# Power_LED_Inducators.net
KiCad netlist of a schematic drawn in Altium Designer
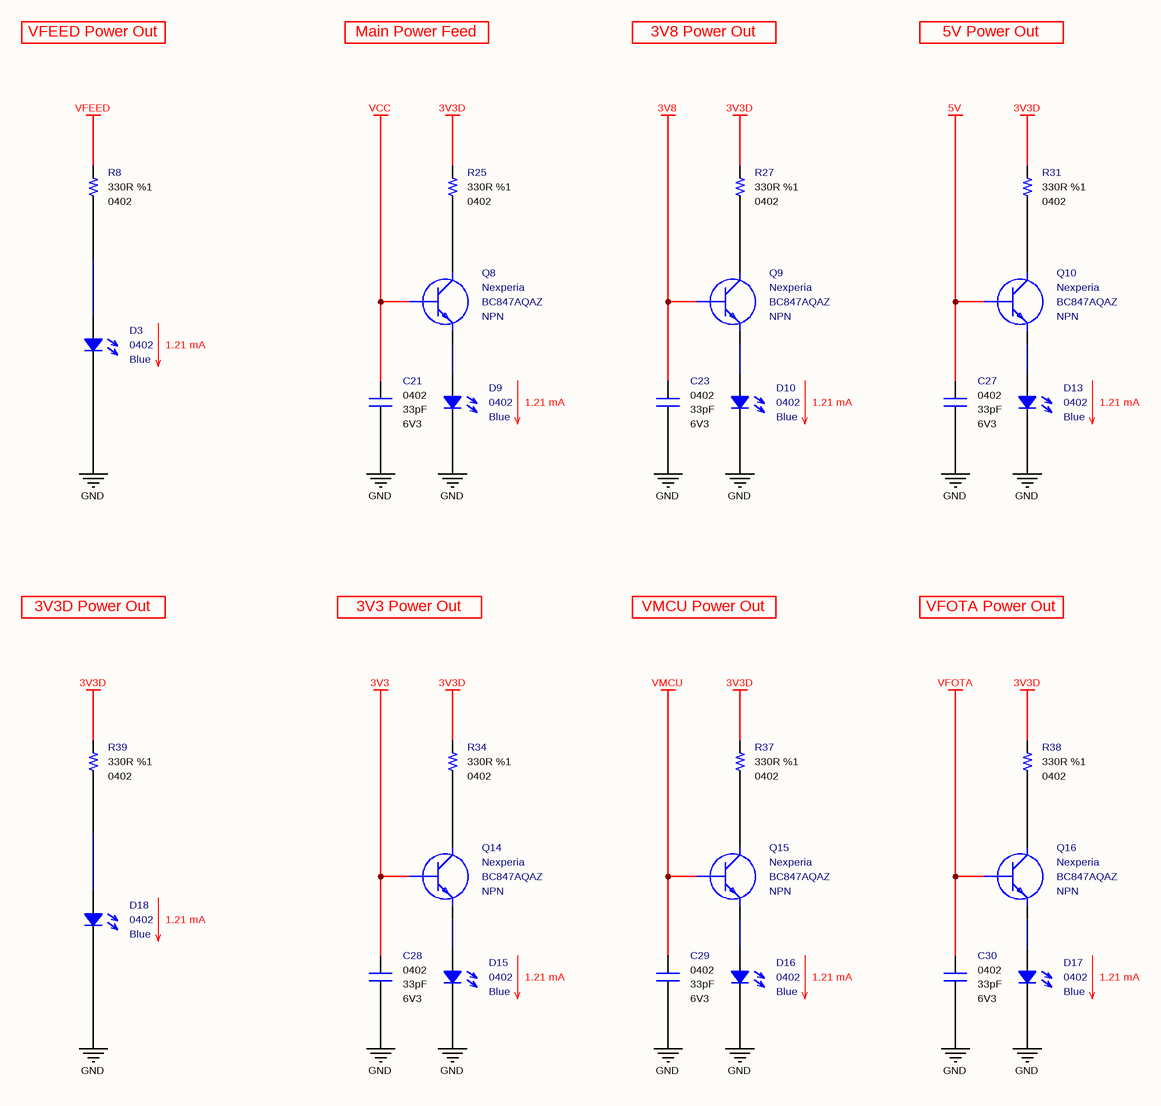
[diagram p0: Power LED Inducators.SchDoc]

(export (version "E")
  (design (tool "Eeschema 10.0.6"))
  (components
    (comp (ref "C21")
      (value "33pF")
      (footprint "CAPACITOR_0402")
      (description "Capacitor - 33pF [0402] (Ceramic)")
      (fields
        (field (name "CASE") "0402")
        (field (name "TOLERANCE") "10%")
        (field (name "VOLTAGE") "6V3")
        (field (name "MANUFACTURER PART NUMBER") "C0402C330J9RACAUTO")
      )
      (libsource (lib "Ovoo_Library") (part "Capacitor - 33pF [0402-6V3]"))
    )
    (comp (ref "C23")
      (value "33pF")
      (footprint "CAPACITOR_0402")
      (description "Capacitor - 33pF [0402] (Ceramic)")
      (fields
        (field (name "CASE") "0402")
        (field (name "TOLERANCE") "10%")
        (field (name "VOLTAGE") "6V3")
        (field (name "MANUFACTURER PART NUMBER") "C0402C330J9RACAUTO")
      )
      (libsource (lib "Ovoo_Library") (part "Capacitor - 33pF [0402-6V3]"))
    )
    (comp (ref "C27")
      (value "33pF")
      (footprint "CAPACITOR_0402")
      (description "Capacitor - 33pF [0402] (Ceramic)")
      (fields
        (field (name "CASE") "0402")
        (field (name "TOLERANCE") "10%")
        (field (name "VOLTAGE") "6V3")
        (field (name "MANUFACTURER PART NUMBER") "C0402C330J9RACAUTO")
      )
      (libsource (lib "Ovoo_Library") (part "Capacitor - 33pF [0402-6V3]"))
    )
    (comp (ref "C28")
      (value "33pF")
      (footprint "CAPACITOR_0402")
      (description "Capacitor - 33pF [0402] (Ceramic)")
      (fields
        (field (name "CASE") "0402")
        (field (name "TOLERANCE") "10%")
        (field (name "VOLTAGE") "6V3")
        (field (name "MANUFACTURER PART NUMBER") "C0402C330J9RACAUTO")
      )
      (libsource (lib "Ovoo_Library") (part "Capacitor - 33pF [0402-6V3]"))
    )
    (comp (ref "C29")
      (value "33pF")
      (footprint "CAPACITOR_0402")
      (description "Capacitor - 33pF [0402] (Ceramic)")
      (fields
        (field (name "CASE") "0402")
        (field (name "TOLERANCE") "10%")
        (field (name "VOLTAGE") "6V3")
        (field (name "MANUFACTURER PART NUMBER") "C0402C330J9RACAUTO")
      )
      (libsource (lib "Ovoo_Library") (part "Capacitor - 33pF [0402-6V3]"))
    )
    (comp (ref "C30")
      (value "33pF")
      (footprint "CAPACITOR_0402")
      (description "Capacitor - 33pF [0402] (Ceramic)")
      (fields
        (field (name "CASE") "0402")
        (field (name "TOLERANCE") "10%")
        (field (name "VOLTAGE") "6V3")
        (field (name "MANUFACTURER PART NUMBER") "C0402C330J9RACAUTO")
      )
      (libsource (lib "Ovoo_Library") (part "Capacitor - 33pF [0402-6V3]"))
    )
    (comp (ref "D3")
      (value "SMD LED (Blue)")
      (footprint "LED_0402")
      (description "Standard LEDs - SMD PICOLEDTM;BLUE LED; 25M @ 5MA")
      (fields
        (field (name "MANUFACTURER_PART_NUMBER") "SMLP13BC8TT86")
        (field (name "MOUSER_PART_NUMBER") "755-SMLP13BC8TT86")
        (field (name "CASE") "0402")
        (field (name "COLOR") "Blue")
      )
      (libsource (lib "Ovoo_Library") (part "Diode - LED (0402-Blue)"))
    )
    (comp (ref "D9")
      (value "SMD LED (Blue)")
      (footprint "LED_0402")
      (description "Standard LEDs - SMD PICOLEDTM;BLUE LED; 25M @ 5MA")
      (fields
        (field (name "MANUFACTURER_PART_NUMBER") "SMLP13BC8TT86")
        (field (name "MOUSER_PART_NUMBER") "755-SMLP13BC8TT86")
        (field (name "CASE") "0402")
        (field (name "COLOR") "Blue")
      )
      (libsource (lib "Ovoo_Library") (part "Diode - LED (0402-Blue)"))
    )
    (comp (ref "D10")
      (value "SMD LED (Blue)")
      (footprint "LED_0402")
      (description "Standard LEDs - SMD PICOLEDTM;BLUE LED; 25M @ 5MA")
      (fields
        (field (name "MANUFACTURER_PART_NUMBER") "SMLP13BC8TT86")
        (field (name "MOUSER_PART_NUMBER") "755-SMLP13BC8TT86")
        (field (name "CASE") "0402")
        (field (name "COLOR") "Blue")
      )
      (libsource (lib "Ovoo_Library") (part "Diode - LED (0402-Blue)"))
    )
    (comp (ref "D13")
      (value "SMD LED (Blue)")
      (footprint "LED_0402")
      (description "Standard LEDs - SMD PICOLEDTM;BLUE LED; 25M @ 5MA")
      (fields
        (field (name "MANUFACTURER_PART_NUMBER") "SMLP13BC8TT86")
        (field (name "MOUSER_PART_NUMBER") "755-SMLP13BC8TT86")
        (field (name "CASE") "0402")
        (field (name "COLOR") "Blue")
      )
      (libsource (lib "Ovoo_Library") (part "Diode - LED (0402-Blue)"))
    )
    (comp (ref "D15")
      (value "SMD LED (Blue)")
      (footprint "LED_0402")
      (description "Standard LEDs - SMD PICOLEDTM;BLUE LED; 25M @ 5MA")
      (fields
        (field (name "MANUFACTURER_PART_NUMBER") "SMLP13BC8TT86")
        (field (name "MOUSER_PART_NUMBER") "755-SMLP13BC8TT86")
        (field (name "CASE") "0402")
        (field (name "COLOR") "Blue")
      )
      (libsource (lib "Ovoo_Library") (part "Diode - LED (0402-Blue)"))
    )
    (comp (ref "D16")
      (value "SMD LED (Blue)")
      (footprint "LED_0402")
      (description "Standard LEDs - SMD PICOLEDTM;BLUE LED; 25M @ 5MA")
      (fields
        (field (name "MANUFACTURER_PART_NUMBER") "SMLP13BC8TT86")
        (field (name "MOUSER_PART_NUMBER") "755-SMLP13BC8TT86")
        (field (name "CASE") "0402")
        (field (name "COLOR") "Blue")
      )
      (libsource (lib "Ovoo_Library") (part "Diode - LED (0402-Blue)"))
    )
    (comp (ref "D17")
      (value "SMD LED (Blue)")
      (footprint "LED_0402")
      (description "Standard LEDs - SMD PICOLEDTM;BLUE LED; 25M @ 5MA")
      (fields
        (field (name "MANUFACTURER_PART_NUMBER") "SMLP13BC8TT86")
        (field (name "MOUSER_PART_NUMBER") "755-SMLP13BC8TT86")
        (field (name "CASE") "0402")
        (field (name "COLOR") "Blue")
      )
      (libsource (lib "Ovoo_Library") (part "Diode - LED (0402-Blue)"))
    )
    (comp (ref "D18")
      (value "SMD LED (Blue)")
      (footprint "LED_0402")
      (description "Standard LEDs - SMD PICOLEDTM;BLUE LED; 25M @ 5MA")
      (fields
        (field (name "MANUFACTURER_PART_NUMBER") "SMLP13BC8TT86")
        (field (name "MOUSER_PART_NUMBER") "755-SMLP13BC8TT86")
        (field (name "CASE") "0402")
        (field (name "COLOR") "Blue")
      )
      (libsource (lib "Ovoo_Library") (part "Diode - LED (0402-Blue)"))
    )
    (comp (ref "Q8")
      (value "Bipolar NPN Transistors")
      (footprint "SOT1215")
      (description "Bipolar Transistors - BJT BC847AQA/DFN1010D-3/REEL 7\" Q2")
      (fields
        (field (name "MOUSER_PART_NUMBER") "771-BC847AQAZ")
        (field (name "MANUFACTURER_NAME") "Nexperia")
        (field (name "MANUFACTURER_PART_NUMBER") "BC847AQAZ")
        (field (name "POLARITY") "NPN")
      )
      (libsource (lib "Ovoo_Library") (part "Transistor - BC847"))
    )
    (comp (ref "Q9")
      (value "Bipolar NPN Transistors")
      (footprint "SOT1215")
      (description "Bipolar Transistors - BJT BC847AQA/DFN1010D-3/REEL 7\" Q2")
      (fields
        (field (name "MOUSER_PART_NUMBER") "771-BC847AQAZ")
        (field (name "MANUFACTURER_NAME") "Nexperia")
        (field (name "MANUFACTURER_PART_NUMBER") "BC847AQAZ")
        (field (name "POLARITY") "NPN")
      )
      (libsource (lib "Ovoo_Library") (part "Transistor - BC847"))
    )
    (comp (ref "Q10")
      (value "Bipolar NPN Transistors")
      (footprint "SOT1215")
      (description "Bipolar Transistors - BJT BC847AQA/DFN1010D-3/REEL 7\" Q2")
      (fields
        (field (name "MOUSER_PART_NUMBER") "771-BC847AQAZ")
        (field (name "MANUFACTURER_NAME") "Nexperia")
        (field (name "MANUFACTURER_PART_NUMBER") "BC847AQAZ")
        (field (name "POLARITY") "NPN")
      )
      (libsource (lib "Ovoo_Library") (part "Transistor - BC847"))
    )
    (comp (ref "Q14")
      (value "Bipolar NPN Transistors")
      (footprint "SOT1215")
      (description "Bipolar Transistors - BJT BC847AQA/DFN1010D-3/REEL 7\" Q2")
      (fields
        (field (name "MOUSER_PART_NUMBER") "771-BC847AQAZ")
        (field (name "MANUFACTURER_NAME") "Nexperia")
        (field (name "MANUFACTURER_PART_NUMBER") "BC847AQAZ")
        (field (name "POLARITY") "NPN")
      )
      (libsource (lib "Ovoo_Library") (part "Transistor - BC847"))
    )
    (comp (ref "Q15")
      (value "Bipolar NPN Transistors")
      (footprint "SOT1215")
      (description "Bipolar Transistors - BJT BC847AQA/DFN1010D-3/REEL 7\" Q2")
      (fields
        (field (name "MOUSER_PART_NUMBER") "771-BC847AQAZ")
        (field (name "MANUFACTURER_NAME") "Nexperia")
        (field (name "MANUFACTURER_PART_NUMBER") "BC847AQAZ")
        (field (name "POLARITY") "NPN")
      )
      (libsource (lib "Ovoo_Library") (part "Transistor - BC847"))
    )
    (comp (ref "Q16")
      (value "Bipolar NPN Transistors")
      (footprint "SOT1215")
      (description "Bipolar Transistors - BJT BC847AQA/DFN1010D-3/REEL 7\" Q2")
      (fields
        (field (name "MOUSER_PART_NUMBER") "771-BC847AQAZ")
        (field (name "MANUFACTURER_NAME") "Nexperia")
        (field (name "MANUFACTURER_PART_NUMBER") "BC847AQAZ")
        (field (name "POLARITY") "NPN")
      )
      (libsource (lib "Ovoo_Library") (part "Transistor - BC847"))
    )
    (comp (ref "R8")
      (value "330R")
      (footprint "RESISTOR_0402")
      (description "Thick Film Resistors - SMD 1/16 W 330 Ohm 1%")
      (fields
        (field (name "TOLERANCE") "%1")
        (field (name "CASE") "0402")
        (field (name "MANUFACTURER PART NUMBER") "CRCW0402330RFKED")
        (field (name "MOUSER PART NUMBER") "71-CRCW0402-330-E3")
      )
      (libsource (lib "Ovoo_Library") (part "Resistor - 330R"))
    )
    (comp (ref "R25")
      (value "330R")
      (footprint "RESISTOR_0402")
      (description "Thick Film Resistors - SMD 1/16 W 330 Ohm 1%")
      (fields
        (field (name "TOLERANCE") "%1")
        (field (name "CASE") "0402")
        (field (name "MANUFACTURER PART NUMBER") "CRCW0402330RFKED")
        (field (name "MOUSER PART NUMBER") "71-CRCW0402-330-E3")
      )
      (libsource (lib "Ovoo_Library") (part "Resistor - 330R"))
    )
    (comp (ref "R27")
      (value "330R")
      (footprint "RESISTOR_0402")
      (description "Thick Film Resistors - SMD 1/16 W 330 Ohm 1%")
      (fields
        (field (name "TOLERANCE") "%1")
        (field (name "CASE") "0402")
        (field (name "MANUFACTURER PART NUMBER") "CRCW0402330RFKED")
        (field (name "MOUSER PART NUMBER") "71-CRCW0402-330-E3")
      )
      (libsource (lib "Ovoo_Library") (part "Resistor - 330R"))
    )
    (comp (ref "R31")
      (value "330R")
      (footprint "RESISTOR_0402")
      (description "Thick Film Resistors - SMD 1/16 W 330 Ohm 1%")
      (fields
        (field (name "TOLERANCE") "%1")
        (field (name "CASE") "0402")
        (field (name "MANUFACTURER PART NUMBER") "CRCW0402330RFKED")
        (field (name "MOUSER PART NUMBER") "71-CRCW0402-330-E3")
      )
      (libsource (lib "Ovoo_Library") (part "Resistor - 330R"))
    )
    (comp (ref "R34")
      (value "330R")
      (footprint "RESISTOR_0402")
      (description "Thick Film Resistors - SMD 1/16 W 330 Ohm 1%")
      (fields
        (field (name "TOLERANCE") "%1")
        (field (name "CASE") "0402")
        (field (name "MANUFACTURER PART NUMBER") "CRCW0402330RFKED")
        (field (name "MOUSER PART NUMBER") "71-CRCW0402-330-E3")
      )
      (libsource (lib "Ovoo_Library") (part "Resistor - 330R"))
    )
    (comp (ref "R37")
      (value "330R")
      (footprint "RESISTOR_0402")
      (description "Thick Film Resistors - SMD 1/16 W 330 Ohm 1%")
      (fields
        (field (name "TOLERANCE") "%1")
        (field (name "CASE") "0402")
        (field (name "MANUFACTURER PART NUMBER") "CRCW0402330RFKED")
        (field (name "MOUSER PART NUMBER") "71-CRCW0402-330-E3")
      )
      (libsource (lib "Ovoo_Library") (part "Resistor - 330R"))
    )
    (comp (ref "R38")
      (value "330R")
      (footprint "RESISTOR_0402")
      (description "Thick Film Resistors - SMD 1/16 W 330 Ohm 1%")
      (fields
        (field (name "TOLERANCE") "%1")
        (field (name "CASE") "0402")
        (field (name "MANUFACTURER PART NUMBER") "CRCW0402330RFKED")
        (field (name "MOUSER PART NUMBER") "71-CRCW0402-330-E3")
      )
      (libsource (lib "Ovoo_Library") (part "Resistor - 330R"))
    )
    (comp (ref "R39")
      (value "330R")
      (footprint "RESISTOR_0402")
      (description "Thick Film Resistors - SMD 1/16 W 330 Ohm 1%")
      (fields
        (field (name "TOLERANCE") "%1")
        (field (name "CASE") "0402")
        (field (name "MANUFACTURER PART NUMBER") "CRCW0402330RFKED")
        (field (name "MOUSER PART NUMBER") "71-CRCW0402-330-E3")
      )
      (libsource (lib "Ovoo_Library") (part "Resistor - 330R"))
    )
  )
  (nets
    (net (code "1") (name "3V3") (class "Default")
      (node (ref "C28") (pin "1") (pinfunction "1_1") (pintype "passive"))
      (node (ref "Q14") (pin "1") (pinfunction "B_1") (pintype "passive"))
    )
    (net (code "2") (name "3V3D") (class "Default")
      (node (ref "R25") (pin "2") (pinfunction "2_2") (pintype "passive"))
      (node (ref "R27") (pin "2") (pinfunction "2_2") (pintype "passive"))
      (node (ref "R31") (pin "2") (pinfunction "2_2") (pintype "passive"))
      (node (ref "R34") (pin "2") (pinfunction "2_2") (pintype "passive"))
      (node (ref "R37") (pin "2") (pinfunction "2_2") (pintype "passive"))
      (node (ref "R38") (pin "2") (pinfunction "2_2") (pintype "passive"))
      (node (ref "R39") (pin "2") (pinfunction "2_2") (pintype "passive"))
    )
    (net (code "3") (name "3V8") (class "Default")
      (node (ref "C23") (pin "1") (pinfunction "1_1") (pintype "passive"))
      (node (ref "Q9") (pin "1") (pinfunction "B_1") (pintype "passive"))
    )
    (net (code "4") (name "5V") (class "Default")
      (node (ref "C27") (pin "1") (pinfunction "1_1") (pintype "passive"))
      (node (ref "Q10") (pin "1") (pinfunction "B_1") (pintype "passive"))
    )
    (net (code "5") (name "GND") (class "Default")
      (node (ref "C21") (pin "2") (pinfunction "2_2") (pintype "passive"))
      (node (ref "C23") (pin "2") (pinfunction "2_2") (pintype "passive"))
      (node (ref "C27") (pin "2") (pinfunction "2_2") (pintype "passive"))
      (node (ref "C28") (pin "2") (pinfunction "2_2") (pintype "passive"))
      (node (ref "C29") (pin "2") (pinfunction "2_2") (pintype "passive"))
      (node (ref "C30") (pin "2") (pinfunction "2_2") (pintype "passive"))
      (node (ref "D10") (pin "1") (pinfunction "1_1") (pintype "passive"))
      (node (ref "D13") (pin "1") (pinfunction "1_1") (pintype "passive"))
      (node (ref "D15") (pin "1") (pinfunction "1_1") (pintype "passive"))
      (node (ref "D16") (pin "1") (pinfunction "1_1") (pintype "passive"))
      (node (ref "D17") (pin "1") (pinfunction "1_1") (pintype "passive"))
      (node (ref "D18") (pin "1") (pinfunction "1_1") (pintype "passive"))
      (node (ref "D3") (pin "1") (pinfunction "1_1") (pintype "passive"))
      (node (ref "D9") (pin "1") (pinfunction "1_1") (pintype "passive"))
    )
    (net (code "6") (name "Net-(D3-Pad2)") (class "Default")
      (node (ref "D3") (pin "2") (pinfunction "2_2") (pintype "passive"))
      (node (ref "R8") (pin "1") (pinfunction "1_1") (pintype "passive"))
    )
    (net (code "7") (name "Net-(D18-Pad2)") (class "Default")
      (node (ref "D18") (pin "2") (pinfunction "2_2") (pintype "passive"))
      (node (ref "R39") (pin "1") (pinfunction "1_1") (pintype "passive"))
    )
    (net (code "8") (name "Net-(Q8-C)") (class "Default")
      (node (ref "Q8") (pin "3") (pinfunction "C_3") (pintype "passive"))
      (node (ref "R25") (pin "1") (pinfunction "1_1") (pintype "passive"))
    )
    (net (code "9") (name "Net-(Q8-E)") (class "Default")
      (node (ref "D9") (pin "2") (pinfunction "2_2") (pintype "passive"))
      (node (ref "Q8") (pin "2") (pinfunction "E_2") (pintype "passive"))
    )
    (net (code "10") (name "Net-(Q9-C)") (class "Default")
      (node (ref "Q9") (pin "3") (pinfunction "C_3") (pintype "passive"))
      (node (ref "R27") (pin "1") (pinfunction "1_1") (pintype "passive"))
    )
    (net (code "11") (name "Net-(Q9-E)") (class "Default")
      (node (ref "D10") (pin "2") (pinfunction "2_2") (pintype "passive"))
      (node (ref "Q9") (pin "2") (pinfunction "E_2") (pintype "passive"))
    )
    (net (code "12") (name "Net-(Q10-C)") (class "Default")
      (node (ref "Q10") (pin "3") (pinfunction "C_3") (pintype "passive"))
      (node (ref "R31") (pin "1") (pinfunction "1_1") (pintype "passive"))
    )
    (net (code "13") (name "Net-(Q10-E)") (class "Default")
      (node (ref "D13") (pin "2") (pinfunction "2_2") (pintype "passive"))
      (node (ref "Q10") (pin "2") (pinfunction "E_2") (pintype "passive"))
    )
    (net (code "14") (name "Net-(Q14-C)") (class "Default")
      (node (ref "Q14") (pin "3") (pinfunction "C_3") (pintype "passive"))
      (node (ref "R34") (pin "1") (pinfunction "1_1") (pintype "passive"))
    )
    (net (code "15") (name "Net-(Q14-E)") (class "Default")
      (node (ref "D15") (pin "2") (pinfunction "2_2") (pintype "passive"))
      (node (ref "Q14") (pin "2") (pinfunction "E_2") (pintype "passive"))
    )
    (net (code "16") (name "Net-(Q15-C)") (class "Default")
      (node (ref "Q15") (pin "3") (pinfunction "C_3") (pintype "passive"))
      (node (ref "R37") (pin "1") (pinfunction "1_1") (pintype "passive"))
    )
    (net (code "17") (name "Net-(Q15-E)") (class "Default")
      (node (ref "D16") (pin "2") (pinfunction "2_2") (pintype "passive"))
      (node (ref "Q15") (pin "2") (pinfunction "E_2") (pintype "passive"))
    )
    (net (code "18") (name "Net-(Q16-C)") (class "Default")
      (node (ref "Q16") (pin "3") (pinfunction "C_3") (pintype "passive"))
      (node (ref "R38") (pin "1") (pinfunction "1_1") (pintype "passive"))
    )
    (net (code "19") (name "Net-(Q16-E)") (class "Default")
      (node (ref "D17") (pin "2") (pinfunction "2_2") (pintype "passive"))
      (node (ref "Q16") (pin "2") (pinfunction "E_2") (pintype "passive"))
    )
    (net (code "20") (name "VCC") (class "Default")
      (node (ref "C21") (pin "1") (pinfunction "1_1") (pintype "passive"))
      (node (ref "Q8") (pin "1") (pinfunction "B_1") (pintype "passive"))
    )
    (net (code "21") (name "VFEED") (class "Default")
      (node (ref "R8") (pin "2") (pinfunction "2_2") (pintype "passive"))
    )
    (net (code "22") (name "VFOTA") (class "Default")
      (node (ref "C30") (pin "1") (pinfunction "1_1") (pintype "passive"))
      (node (ref "Q16") (pin "1") (pinfunction "B_1") (pintype "passive"))
    )
    (net (code "23") (name "VMCU") (class "Default")
      (node (ref "C29") (pin "1") (pinfunction "1_1") (pintype "passive"))
      (node (ref "Q15") (pin "1") (pinfunction "B_1") (pintype "passive"))
    )
  )
)
